# SOM_AB.net
KiCad netlist of a schematic drawn in Altium Designer
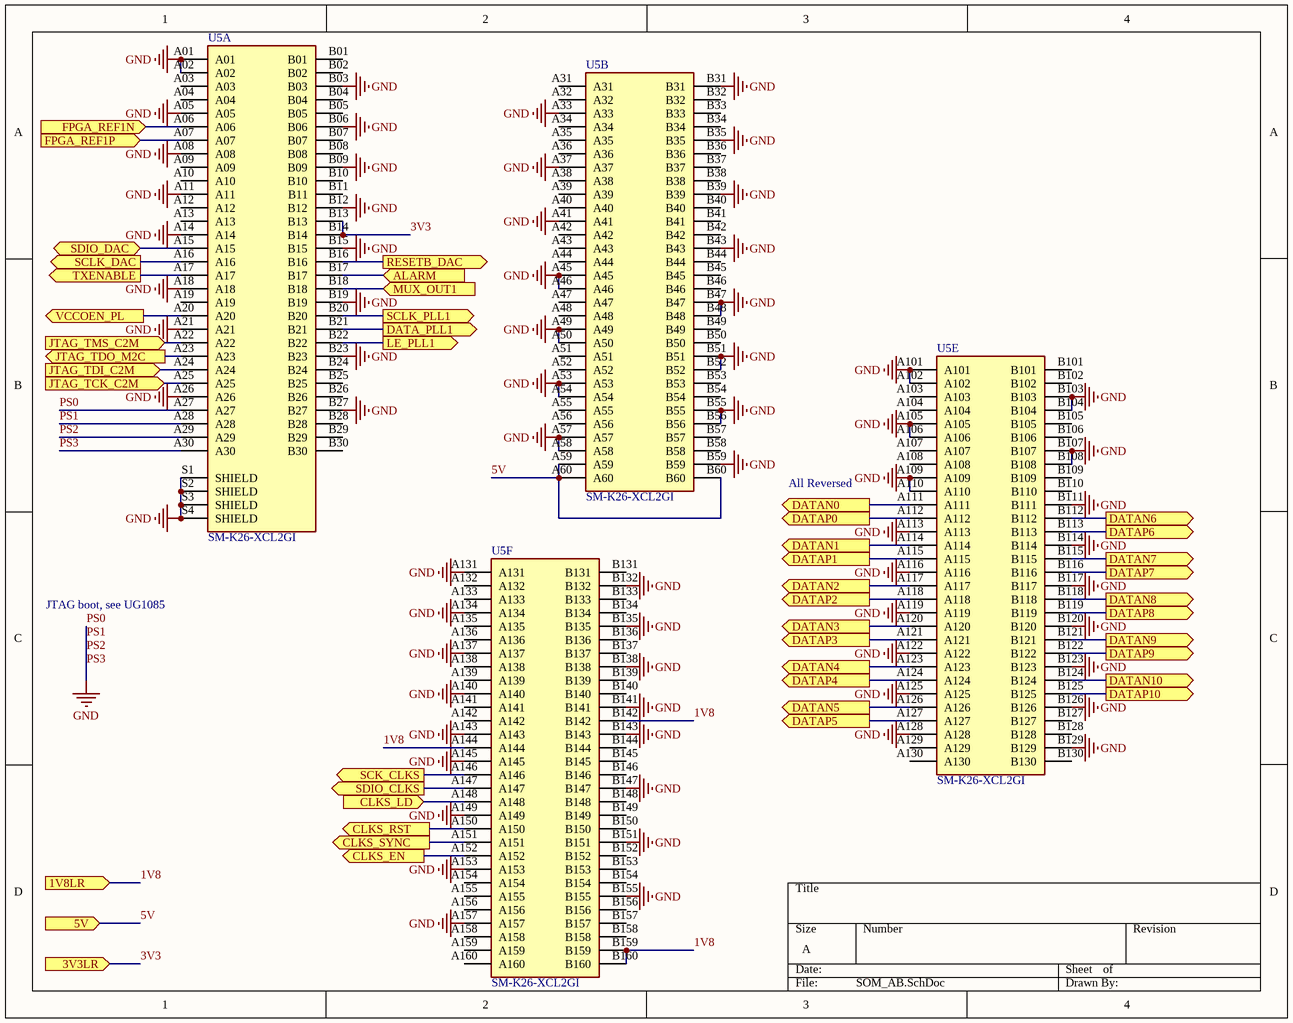
[diagram p0: SOM_AB.SchDoc]

(export (version "E")
  (design (tool "Eeschema 10.0.6"))
  (components
    (comp (ref "U5")
      (value "SM-K26-XCL2GI")
      (footprint "MODULE_SM-K26-XCL2GI")
      (fields (field (name "MF") "Xilinx Inc."))
      (libsource (lib "SM-K26-XCL2GI") (part "SM-K26-XCL2GI"))
    )
  )
  (nets
    (net (code "1") (name "/1V8") (class "Default")
      (node (ref "U5") (pin "A144") (pinfunction "A144_A144") (pintype "passive"))
      (node (ref "U5") (pin "B142") (pinfunction "B142_B142") (pintype "passive"))
      (node (ref "U5") (pin "B159") (pinfunction "B159_B159") (pintype "passive"))
      (node (ref "U5") (pin "B160") (pinfunction "B160_B160") (pintype "passive"))
    )
    (net (code "2") (name "/3V3") (class "Default")
      (node (ref "U5") (pin "B13") (pinfunction "B13_B13") (pintype "passive"))
      (node (ref "U5") (pin "B14") (pinfunction "B14_B14") (pintype "passive"))
    )
    (net (code "3") (name "/5V") (class "Default")
      (node (ref "U5") (pin "A59") (pinfunction "A59_A59") (pintype "passive"))
      (node (ref "U5") (pin "A60") (pinfunction "A60_A60") (pintype "passive"))
      (node (ref "U5") (pin "B60") (pinfunction "B60_B60") (pintype "passive"))
    )
    (net (code "4") (name "/ALARM") (class "Default")
      (node (ref "U5") (pin "B17") (pinfunction "B17_B17") (pintype "passive"))
    )
    (net (code "5") (name "/CLKS_EN") (class "Default")
      (node (ref "U5") (pin "A152") (pinfunction "A152_A152") (pintype "passive"))
    )
    (net (code "6") (name "/CLKS_LD") (class "Default")
      (node (ref "U5") (pin "A148") (pinfunction "A148_A148") (pintype "passive"))
    )
    (net (code "7") (name "/CLKS_RST") (class "Default")
      (node (ref "U5") (pin "A150") (pinfunction "A150_A150") (pintype "passive"))
    )
    (net (code "8") (name "/CLKS_SYNC") (class "Default")
      (node (ref "U5") (pin "A151") (pinfunction "A151_A151") (pintype "passive"))
    )
    (net (code "9") (name "/DATAN0") (class "Default")
      (node (ref "U5") (pin "A111") (pinfunction "A111_A111") (pintype "passive"))
    )
    (net (code "10") (name "/DATAN1") (class "Default")
      (node (ref "U5") (pin "A114") (pinfunction "A114_A114") (pintype "passive"))
    )
    (net (code "11") (name "/DATAN2") (class "Default")
      (node (ref "U5") (pin "A117") (pinfunction "A117_A117") (pintype "passive"))
    )
    (net (code "12") (name "/DATAN3") (class "Default")
      (node (ref "U5") (pin "A120") (pinfunction "A120_A120") (pintype "passive"))
    )
    (net (code "13") (name "/DATAN4") (class "Default")
      (node (ref "U5") (pin "A123") (pinfunction "A123_A123") (pintype "passive"))
    )
    (net (code "14") (name "/DATAN5") (class "Default")
      (node (ref "U5") (pin "A126") (pinfunction "A126_A126") (pintype "passive"))
    )
    (net (code "15") (name "/DATAN6") (class "Default")
      (node (ref "U5") (pin "B112") (pinfunction "B112_B112") (pintype "passive"))
    )
    (net (code "16") (name "/DATAN7") (class "Default")
      (node (ref "U5") (pin "B115") (pinfunction "B115_B115") (pintype "passive"))
    )
    (net (code "17") (name "/DATAN8") (class "Default")
      (node (ref "U5") (pin "B118") (pinfunction "B118_B118") (pintype "passive"))
    )
    (net (code "18") (name "/DATAN9") (class "Default")
      (node (ref "U5") (pin "B121") (pinfunction "B121_B121") (pintype "passive"))
    )
    (net (code "19") (name "/DATAN10") (class "Default")
      (node (ref "U5") (pin "B124") (pinfunction "B124_B124") (pintype "passive"))
    )
    (net (code "20") (name "/DATAP0") (class "Default")
      (node (ref "U5") (pin "A112") (pinfunction "A112_A112") (pintype "passive"))
    )
    (net (code "21") (name "/DATAP1") (class "Default")
      (node (ref "U5") (pin "A115") (pinfunction "A115_A115") (pintype "passive"))
    )
    (net (code "22") (name "/DATAP2") (class "Default")
      (node (ref "U5") (pin "A118") (pinfunction "A118_A118") (pintype "passive"))
    )
    (net (code "23") (name "/DATAP3") (class "Default")
      (node (ref "U5") (pin "A121") (pinfunction "A121_A121") (pintype "passive"))
    )
    (net (code "24") (name "/DATAP4") (class "Default")
      (node (ref "U5") (pin "A124") (pinfunction "A124_A124") (pintype "passive"))
    )
    (net (code "25") (name "/DATAP5") (class "Default")
      (node (ref "U5") (pin "A127") (pinfunction "A127_A127") (pintype "passive"))
    )
    (net (code "26") (name "/DATAP6") (class "Default")
      (node (ref "U5") (pin "B113") (pinfunction "B113_B113") (pintype "passive"))
    )
    (net (code "27") (name "/DATAP7") (class "Default")
      (node (ref "U5") (pin "B116") (pinfunction "B116_B116") (pintype "passive"))
    )
    (net (code "28") (name "/DATAP8") (class "Default")
      (node (ref "U5") (pin "B119") (pinfunction "B119_B119") (pintype "passive"))
    )
    (net (code "29") (name "/DATAP9") (class "Default")
      (node (ref "U5") (pin "B122") (pinfunction "B122_B122") (pintype "passive"))
    )
    (net (code "30") (name "/DATAP10") (class "Default")
      (node (ref "U5") (pin "B125") (pinfunction "B125_B125") (pintype "passive"))
    )
    (net (code "31") (name "/DATA_PLL1") (class "Default")
      (node (ref "U5") (pin "B21") (pinfunction "B21_B21") (pintype "passive"))
    )
    (net (code "32") (name "/FPGA_REF1N") (class "Default")
      (node (ref "U5") (pin "A06") (pinfunction "A06_A06") (pintype "passive"))
    )
    (net (code "33") (name "/FPGA_REF1P") (class "Default")
      (node (ref "U5") (pin "A07") (pinfunction "A07_A07") (pintype "passive"))
    )
    (net (code "34") (name "/JTAG_TCK_C2M") (class "Default")
      (node (ref "U5") (pin "A25") (pinfunction "A25_A25") (pintype "passive"))
    )
    (net (code "35") (name "/JTAG_TDI_C2M") (class "Default")
      (node (ref "U5") (pin "A24") (pinfunction "A24_A24") (pintype "passive"))
    )
    (net (code "36") (name "/JTAG_TDO_M2C") (class "Default")
      (node (ref "U5") (pin "A23") (pinfunction "A23_A23") (pintype "passive"))
    )
    (net (code "37") (name "/JTAG_TMS_C2M") (class "Default")
      (node (ref "U5") (pin "A22") (pinfunction "A22_A22") (pintype "passive"))
    )
    (net (code "38") (name "/LE_PLL1") (class "Default")
      (node (ref "U5") (pin "B22") (pinfunction "B22_B22") (pintype "passive"))
    )
    (net (code "39") (name "/MUX_OUT1") (class "Default")
      (node (ref "U5") (pin "B18") (pinfunction "B18_B18") (pintype "passive"))
    )
    (net (code "40") (name "/RESETB_DAC") (class "Default")
      (node (ref "U5") (pin "B16") (pinfunction "B16_B16") (pintype "passive"))
    )
    (net (code "41") (name "/SCK_CLKS") (class "Default")
      (node (ref "U5") (pin "A146") (pinfunction "A146_A146") (pintype "passive"))
    )
    (net (code "42") (name "/SCLK_DAC") (class "Default")
      (node (ref "U5") (pin "A16") (pinfunction "A16_A16") (pintype "passive"))
    )
    (net (code "43") (name "/SCLK_PLL1") (class "Default")
      (node (ref "U5") (pin "B20") (pinfunction "B20_B20") (pintype "passive"))
    )
    (net (code "44") (name "/SDIO_CLKS") (class "Default")
      (node (ref "U5") (pin "A147") (pinfunction "A147_A147") (pintype "passive"))
    )
    (net (code "45") (name "/SDIO_DAC") (class "Default")
      (node (ref "U5") (pin "A15") (pinfunction "A15_A15") (pintype "passive"))
    )
    (net (code "46") (name "/TXENABLE") (class "Default")
      (node (ref "U5") (pin "A17") (pinfunction "A17_A17") (pintype "passive"))
    )
    (net (code "47") (name "/VCCOEN_PL") (class "Default")
      (node (ref "U5") (pin "A20") (pinfunction "A20_A20") (pintype "passive"))
    )
    (net (code "48") (name "GND") (class "Default")
      (node (ref "U5") (pin "A01") (pinfunction "A01_A01") (pintype "passive"))
      (node (ref "U5") (pin "A02") (pinfunction "A02_A02") (pintype "passive"))
      (node (ref "U5") (pin "A05") (pinfunction "A05_A05") (pintype "passive"))
      (node (ref "U5") (pin "A08") (pinfunction "A08_A08") (pintype "passive"))
      (node (ref "U5") (pin "A101") (pinfunction "A101_A101") (pintype "passive"))
      (node (ref "U5") (pin "A102") (pinfunction "A102_A102") (pintype "passive"))
      (node (ref "U5") (pin "A105") (pinfunction "A105_A105") (pintype "passive"))
      (node (ref "U5") (pin "A106") (pinfunction "A106_A106") (pintype "passive"))
      (node (ref "U5") (pin "A109") (pinfunction "A109_A109") (pintype "passive"))
      (node (ref "U5") (pin "A11") (pinfunction "A11_A11") (pintype "passive"))
      (node (ref "U5") (pin "A110") (pinfunction "A110_A110") (pintype "passive"))
      (node (ref "U5") (pin "A113") (pinfunction "A113_A113") (pintype "passive"))
      (node (ref "U5") (pin "A116") (pinfunction "A116_A116") (pintype "passive"))
      (node (ref "U5") (pin "A119") (pinfunction "A119_A119") (pintype "passive"))
      (node (ref "U5") (pin "A122") (pinfunction "A122_A122") (pintype "passive"))
      (node (ref "U5") (pin "A125") (pinfunction "A125_A125") (pintype "passive"))
      (node (ref "U5") (pin "A128") (pinfunction "A128_A128") (pintype "passive"))
      (node (ref "U5") (pin "A131") (pinfunction "A131_A131") (pintype "passive"))
      (node (ref "U5") (pin "A134") (pinfunction "A134_A134") (pintype "passive"))
      (node (ref "U5") (pin "A137") (pinfunction "A137_A137") (pintype "passive"))
      (node (ref "U5") (pin "A14") (pinfunction "A14_A14") (pintype "passive"))
      (node (ref "U5") (pin "A140") (pinfunction "A140_A140") (pintype "passive"))
      (node (ref "U5") (pin "A143") (pinfunction "A143_A143") (pintype "passive"))
      (node (ref "U5") (pin "A145") (pinfunction "A145_A145") (pintype "passive"))
      (node (ref "U5") (pin "A149") (pinfunction "A149_A149") (pintype "passive"))
      (node (ref "U5") (pin "A153") (pinfunction "A153_A153") (pintype "passive"))
      (node (ref "U5") (pin "A157") (pinfunction "A157_A157") (pintype "passive"))
      (node (ref "U5") (pin "A18") (pinfunction "A18_A18") (pintype "passive"))
      (node (ref "U5") (pin "A21") (pinfunction "A21_A21") (pintype "passive"))
      (node (ref "U5") (pin "A26") (pinfunction "A26_A26") (pintype "passive"))
      (node (ref "U5") (pin "A27") (pinfunction "A27_A27") (pintype "passive"))
      (node (ref "U5") (pin "A28") (pinfunction "A28_A28") (pintype "passive"))
      (node (ref "U5") (pin "A29") (pinfunction "A29_A29") (pintype "passive"))
      (node (ref "U5") (pin "A30") (pinfunction "A30_A30") (pintype "passive"))
      (node (ref "U5") (pin "A33") (pinfunction "A33_A33") (pintype "passive"))
      (node (ref "U5") (pin "A37") (pinfunction "A37_A37") (pintype "passive"))
      (node (ref "U5") (pin "A41") (pinfunction "A41_A41") (pintype "passive"))
      (node (ref "U5") (pin "A45") (pinfunction "A45_A45") (pintype "passive"))
      (node (ref "U5") (pin "A46") (pinfunction "A46_A46") (pintype "passive"))
      (node (ref "U5") (pin "A49") (pinfunction "A49_A49") (pintype "passive"))
      (node (ref "U5") (pin "A50") (pinfunction "A50_A50") (pintype "passive"))
      (node (ref "U5") (pin "A53") (pinfunction "A53_A53") (pintype "passive"))
      (node (ref "U5") (pin "A54") (pinfunction "A54_A54") (pintype "passive"))
      (node (ref "U5") (pin "A57") (pinfunction "A57_A57") (pintype "passive"))
      (node (ref "U5") (pin "A58") (pinfunction "A58_A58") (pintype "passive"))
      (node (ref "U5") (pin "B03") (pinfunction "B03_B03") (pintype "passive"))
      (node (ref "U5") (pin "B06") (pinfunction "B06_B06") (pintype "passive"))
      (node (ref "U5") (pin "B09") (pinfunction "B09_B09") (pintype "passive"))
      (node (ref "U5") (pin "B103") (pinfunction "B103_B103") (pintype "passive"))
      (node (ref "U5") (pin "B104") (pinfunction "B104_B104") (pintype "passive"))
      (node (ref "U5") (pin "B107") (pinfunction "B107_B107") (pintype "passive"))
      (node (ref "U5") (pin "B108") (pinfunction "B108_B108") (pintype "passive"))
      (node (ref "U5") (pin "B111") (pinfunction "B111_B111") (pintype "passive"))
      (node (ref "U5") (pin "B114") (pinfunction "B114_B114") (pintype "passive"))
      (node (ref "U5") (pin "B117") (pinfunction "B117_B117") (pintype "passive"))
      (node (ref "U5") (pin "B12") (pinfunction "B12_B12") (pintype "passive"))
      (node (ref "U5") (pin "B120") (pinfunction "B120_B120") (pintype "passive"))
      (node (ref "U5") (pin "B123") (pinfunction "B123_B123") (pintype "passive"))
      (node (ref "U5") (pin "B126") (pinfunction "B126_B126") (pintype "passive"))
      (node (ref "U5") (pin "B129") (pinfunction "B129_B129") (pintype "passive"))
      (node (ref "U5") (pin "B132") (pinfunction "B132_B132") (pintype "passive"))
      (node (ref "U5") (pin "B135") (pinfunction "B135_B135") (pintype "passive"))
      (node (ref "U5") (pin "B138") (pinfunction "B138_B138") (pintype "passive"))
      (node (ref "U5") (pin "B141") (pinfunction "B141_B141") (pintype "passive"))
      (node (ref "U5") (pin "B143") (pinfunction "B143_B143") (pintype "passive"))
      (node (ref "U5") (pin "B147") (pinfunction "B147_B147") (pintype "passive"))
      (node (ref "U5") (pin "B15") (pinfunction "B15_B15") (pintype "passive"))
      (node (ref "U5") (pin "B151") (pinfunction "B151_B151") (pintype "passive"))
      (node (ref "U5") (pin "B155") (pinfunction "B155_B155") (pintype "passive"))
      (node (ref "U5") (pin "B19") (pinfunction "B19_B19") (pintype "passive"))
      (node (ref "U5") (pin "B23") (pinfunction "B23_B23") (pintype "passive"))
      (node (ref "U5") (pin "B27") (pinfunction "B27_B27") (pintype "passive"))
      (node (ref "U5") (pin "B31") (pinfunction "B31_B31") (pintype "passive"))
      (node (ref "U5") (pin "B35") (pinfunction "B35_B35") (pintype "passive"))
      (node (ref "U5") (pin "B39") (pinfunction "B39_B39") (pintype "passive"))
      (node (ref "U5") (pin "B43") (pinfunction "B43_B43") (pintype "passive"))
      (node (ref "U5") (pin "B47") (pinfunction "B47_B47") (pintype "passive"))
      (node (ref "U5") (pin "B48") (pinfunction "B48_B48") (pintype "passive"))
      (node (ref "U5") (pin "B51") (pinfunction "B51_B51") (pintype "passive"))
      (node (ref "U5") (pin "B52") (pinfunction "B52_B52") (pintype "passive"))
      (node (ref "U5") (pin "B55") (pinfunction "B55_B55") (pintype "passive"))
      (node (ref "U5") (pin "B56") (pinfunction "B56_B56") (pintype "passive"))
      (node (ref "U5") (pin "B59") (pinfunction "B59_B59") (pintype "passive"))
      (node (ref "U5") (pin "S1") (pinfunction "SHIELD_S1") (pintype "passive"))
      (node (ref "U5") (pin "S2") (pinfunction "SHIELD_S2") (pintype "passive"))
      (node (ref "U5") (pin "S3") (pinfunction "SHIELD_S3") (pintype "passive"))
      (node (ref "U5") (pin "S4") (pinfunction "SHIELD_S4") (pintype "passive"))
    )
    (net (code "49") (name "unconnected-(U5-PadA03)") (class "Default")
      (node (ref "U5") (pin "A03") (pinfunction "A03_A03") (pintype "passive"))
    )
    (net (code "50") (name "unconnected-(U5-PadA04)") (class "Default")
      (node (ref "U5") (pin "A04") (pinfunction "A04_A04") (pintype "passive"))
    )
    (net (code "51") (name "unconnected-(U5-PadA09)") (class "Default")
      (node (ref "U5") (pin "A09") (pinfunction "A09_A09") (pintype "passive"))
    )
    (net (code "52") (name "unconnected-(U5-PadA10)") (class "Default")
      (node (ref "U5") (pin "A10") (pinfunction "A10_A10") (pintype "passive"))
    )
    (net (code "53") (name "unconnected-(U5-PadA12)") (class "Default")
      (node (ref "U5") (pin "A12") (pinfunction "A12_A12") (pintype "passive"))
    )
    (net (code "54") (name "unconnected-(U5-PadA13)") (class "Default")
      (node (ref "U5") (pin "A13") (pinfunction "A13_A13") (pintype "passive"))
    )
    (net (code "55") (name "unconnected-(U5-PadA19)") (class "Default")
      (node (ref "U5") (pin "A19") (pinfunction "A19_A19") (pintype "passive"))
    )
    (net (code "56") (name "unconnected-(U5-PadA31)") (class "Default")
      (node (ref "U5") (pin "A31") (pinfunction "A31_A31") (pintype "passive"))
    )
    (net (code "57") (name "unconnected-(U5-PadA32)") (class "Default")
      (node (ref "U5") (pin "A32") (pinfunction "A32_A32") (pintype "passive"))
    )
    (net (code "58") (name "unconnected-(U5-PadA34)") (class "Default")
      (node (ref "U5") (pin "A34") (pinfunction "A34_A34") (pintype "passive"))
    )
    (net (code "59") (name "unconnected-(U5-PadA35)") (class "Default")
      (node (ref "U5") (pin "A35") (pinfunction "A35_A35") (pintype "passive"))
    )
    (net (code "60") (name "unconnected-(U5-PadA36)") (class "Default")
      (node (ref "U5") (pin "A36") (pinfunction "A36_A36") (pintype "passive"))
    )
    (net (code "61") (name "unconnected-(U5-PadA38)") (class "Default")
      (node (ref "U5") (pin "A38") (pinfunction "A38_A38") (pintype "passive"))
    )
    (net (code "62") (name "unconnected-(U5-PadA39)") (class "Default")
      (node (ref "U5") (pin "A39") (pinfunction "A39_A39") (pintype "passive"))
    )
    (net (code "63") (name "unconnected-(U5-PadA40)") (class "Default")
      (node (ref "U5") (pin "A40") (pinfunction "A40_A40") (pintype "passive"))
    )
    (net (code "64") (name "unconnected-(U5-PadA42)") (class "Default")
      (node (ref "U5") (pin "A42") (pinfunction "A42_A42") (pintype "passive"))
    )
    (net (code "65") (name "unconnected-(U5-PadA43)") (class "Default")
      (node (ref "U5") (pin "A43") (pinfunction "A43_A43") (pintype "passive"))
    )
    (net (code "66") (name "unconnected-(U5-PadA44)") (class "Default")
      (node (ref "U5") (pin "A44") (pinfunction "A44_A44") (pintype "passive"))
    )
    (net (code "67") (name "unconnected-(U5-PadA47)") (class "Default")
      (node (ref "U5") (pin "A47") (pinfunction "A47_A47") (pintype "passive"))
    )
    (net (code "68") (name "unconnected-(U5-PadA48)") (class "Default")
      (node (ref "U5") (pin "A48") (pinfunction "A48_A48") (pintype "passive"))
    )
    (net (code "69") (name "unconnected-(U5-PadA51)") (class "Default")
      (node (ref "U5") (pin "A51") (pinfunction "A51_A51") (pintype "passive"))
    )
    (net (code "70") (name "unconnected-(U5-PadA52)") (class "Default")
      (node (ref "U5") (pin "A52") (pinfunction "A52_A52") (pintype "passive"))
    )
    (net (code "71") (name "unconnected-(U5-PadA55)") (class "Default")
      (node (ref "U5") (pin "A55") (pinfunction "A55_A55") (pintype "passive"))
    )
    (net (code "72") (name "unconnected-(U5-PadA56)") (class "Default")
      (node (ref "U5") (pin "A56") (pinfunction "A56_A56") (pintype "passive"))
    )
    (net (code "73") (name "unconnected-(U5-PadA103)") (class "Default")
      (node (ref "U5") (pin "A103") (pinfunction "A103_A103") (pintype "passive"))
    )
    (net (code "74") (name "unconnected-(U5-PadA104)") (class "Default")
      (node (ref "U5") (pin "A104") (pinfunction "A104_A104") (pintype "passive"))
    )
    (net (code "75") (name "unconnected-(U5-PadA107)") (class "Default")
      (node (ref "U5") (pin "A107") (pinfunction "A107_A107") (pintype "passive"))
    )
    (net (code "76") (name "unconnected-(U5-PadA108)") (class "Default")
      (node (ref "U5") (pin "A108") (pinfunction "A108_A108") (pintype "passive"))
    )
    (net (code "77") (name "unconnected-(U5-PadA129)") (class "Default")
      (node (ref "U5") (pin "A129") (pinfunction "A129_A129") (pintype "passive"))
    )
    (net (code "78") (name "unconnected-(U5-PadA130)") (class "Default")
      (node (ref "U5") (pin "A130") (pinfunction "A130_A130") (pintype "passive"))
    )
    (net (code "79") (name "unconnected-(U5-PadA132)") (class "Default")
      (node (ref "U5") (pin "A132") (pinfunction "A132_A132") (pintype "passive"))
    )
    (net (code "80") (name "unconnected-(U5-PadA133)") (class "Default")
      (node (ref "U5") (pin "A133") (pinfunction "A133_A133") (pintype "passive"))
    )
    (net (code "81") (name "unconnected-(U5-PadA135)") (class "Default")
      (node (ref "U5") (pin "A135") (pinfunction "A135_A135") (pintype "passive"))
    )
    (net (code "82") (name "unconnected-(U5-PadA136)") (class "Default")
      (node (ref "U5") (pin "A136") (pinfunction "A136_A136") (pintype "passive"))
    )
    (net (code "83") (name "unconnected-(U5-PadA138)") (class "Default")
      (node (ref "U5") (pin "A138") (pinfunction "A138_A138") (pintype "passive"))
    )
    (net (code "84") (name "unconnected-(U5-PadA139)") (class "Default")
      (node (ref "U5") (pin "A139") (pinfunction "A139_A139") (pintype "passive"))
    )
    (net (code "85") (name "unconnected-(U5-PadA141)") (class "Default")
      (node (ref "U5") (pin "A141") (pinfunction "A141_A141") (pintype "passive"))
    )
    (net (code "86") (name "unconnected-(U5-PadA142)") (class "Default")
      (node (ref "U5") (pin "A142") (pinfunction "A142_A142") (pintype "passive"))
    )
    (net (code "87") (name "unconnected-(U5-PadA154)") (class "Default")
      (node (ref "U5") (pin "A154") (pinfunction "A154_A154") (pintype "passive"))
    )
    (net (code "88") (name "unconnected-(U5-PadA155)") (class "Default")
      (node (ref "U5") (pin "A155") (pinfunction "A155_A155") (pintype "passive"))
    )
    (net (code "89") (name "unconnected-(U5-PadA156)") (class "Default")
      (node (ref "U5") (pin "A156") (pinfunction "A156_A156") (pintype "passive"))
    )
    (net (code "90") (name "unconnected-(U5-PadA158)") (class "Default")
      (node (ref "U5") (pin "A158") (pinfunction "A158_A158") (pintype "passive"))
    )
    (net (code "91") (name "unconnected-(U5-PadA159)") (class "Default")
      (node (ref "U5") (pin "A159") (pinfunction "A159_A159") (pintype "passive"))
    )
    (net (code "92") (name "unconnected-(U5-PadA160)") (class "Default")
      (node (ref "U5") (pin "A160") (pinfunction "A160_A160") (pintype "passive"))
    )
    (net (code "93") (name "unconnected-(U5-PadB01)") (class "Default")
      (node (ref "U5") (pin "B01") (pinfunction "B01_B01") (pintype "passive"))
    )
    (net (code "94") (name "unconnected-(U5-PadB02)") (class "Default")
      (node (ref "U5") (pin "B02") (pinfunction "B02_B02") (pintype "passive"))
    )
    (net (code "95") (name "unconnected-(U5-PadB04)") (class "Default")
      (node (ref "U5") (pin "B04") (pinfunction "B04_B04") (pintype "passive"))
    )
    (net (code "96") (name "unconnected-(U5-PadB05)") (class "Default")
      (node (ref "U5") (pin "B05") (pinfunction "B05_B05") (pintype "passive"))
    )
    (net (code "97") (name "unconnected-(U5-PadB07)") (class "Default")
      (node (ref "U5") (pin "B07") (pinfunction "B07_B07") (pintype "passive"))
    )
    (net (code "98") (name "unconnected-(U5-PadB08)") (class "Default")
      (node (ref "U5") (pin "B08") (pinfunction "B08_B08") (pintype "passive"))
    )
    (net (code "99") (name "unconnected-(U5-PadB10)") (class "Default")
      (node (ref "U5") (pin "B10") (pinfunction "B10_B10") (pintype "passive"))
    )
    (net (code "100") (name "unconnected-(U5-PadB11)") (class "Default")
      (node (ref "U5") (pin "B11") (pinfunction "B11_B11") (pintype "passive"))
    )
    (net (code "101") (name "unconnected-(U5-PadB24)") (class "Default")
      (node (ref "U5") (pin "B24") (pinfunction "B24_B24") (pintype "passive"))
    )
    (net (code "102") (name "unconnected-(U5-PadB25)") (class "Default")
      (node (ref "U5") (pin "B25") (pinfunction "B25_B25") (pintype "passive"))
    )
    (net (code "103") (name "unconnected-(U5-PadB26)") (class "Default")
      (node (ref "U5") (pin "B26") (pinfunction "B26_B26") (pintype "passive"))
    )
    (net (code "104") (name "unconnected-(U5-PadB28)") (class "Default")
      (node (ref "U5") (pin "B28") (pinfunction "B28_B28") (pintype "passive"))
    )
    (net (code "105") (name "unconnected-(U5-PadB29)") (class "Default")
      (node (ref "U5") (pin "B29") (pinfunction "B29_B29") (pintype "passive"))
    )
    (net (code "106") (name "unconnected-(U5-PadB30)") (class "Default")
      (node (ref "U5") (pin "B30") (pinfunction "B30_B30") (pintype "passive"))
    )
    (net (code "107") (name "unconnected-(U5-PadB32)") (class "Default")
      (node (ref "U5") (pin "B32") (pinfunction "B32_B32") (pintype "passive"))
    )
    (net (code "108") (name "unconnected-(U5-PadB33)") (class "Default")
      (node (ref "U5") (pin "B33") (pinfunction "B33_B33") (pintype "passive"))
    )
    (net (code "109") (name "unconnected-(U5-PadB34)") (class "Default")
      (node (ref "U5") (pin "B34") (pinfunction "B34_B34") (pintype "passive"))
    )
    (net (code "110") (name "unconnected-(U5-PadB36)") (class "Default")
      (node (ref "U5") (pin "B36") (pinfunction "B36_B36") (pintype "passive"))
    )
    (net (code "111") (name "unconnected-(U5-PadB37)") (class "Default")
      (node (ref "U5") (pin "B37") (pinfunction "B37_B37") (pintype "passive"))
    )
    (net (code "112") (name "unconnected-(U5-PadB38)") (class "Default")
      (node (ref "U5") (pin "B38") (pinfunction "B38_B38") (pintype "passive"))
    )
    (net (code "113") (name "unconnected-(U5-PadB40)") (class "Default")
      (node (ref "U5") (pin "B40") (pinfunction "B40_B40") (pintype "passive"))
    )
    (net (code "114") (name "unconnected-(U5-PadB41)") (class "Default")
      (node (ref "U5") (pin "B41") (pinfunction "B41_B41") (pintype "passive"))
    )
    (net (code "115") (name "unconnected-(U5-PadB42)") (class "Default")
      (node (ref "U5") (pin "B42") (pinfunction "B42_B42") (pintype "passive"))
    )
    (net (code "116") (name "unconnected-(U5-PadB44)") (class "Default")
      (node (ref "U5") (pin "B44") (pinfunction "B44_B44") (pintype "passive"))
    )
    (net (code "117") (name "unconnected-(U5-PadB45)") (class "Default")
      (node (ref "U5") (pin "B45") (pinfunction "B45_B45") (pintype "passive"))
    )
    (net (code "118") (name "unconnected-(U5-PadB46)") (class "Default")
      (node (ref "U5") (pin "B46") (pinfunction "B46_B46") (pintype "passive"))
    )
    (net (code "119") (name "unconnected-(U5-PadB49)") (class "Default")
      (node (ref "U5") (pin "B49") (pinfunction "B49_B49") (pintype "passive"))
    )
    (net (code "120") (name "unconnected-(U5-PadB50)") (class "Default")
      (node (ref "U5") (pin "B50") (pinfunction "B50_B50") (pintype "passive"))
    )
    (net (code "121") (name "unconnected-(U5-PadB53)") (class "Default")
      (node (ref "U5") (pin "B53") (pinfunction "B53_B53") (pintype "passive"))
    )
    (net (code "122") (name "unconnected-(U5-PadB54)") (class "Default")
      (node (ref "U5") (pin "B54") (pinfunction "B54_B54") (pintype "passive"))
    )
    (net (code "123") (name "unconnected-(U5-PadB57)") (class "Default")
      (node (ref "U5") (pin "B57") (pinfunction "B57_B57") (pintype "passive"))
    )
    (net (code "124") (name "unconnected-(U5-PadB58)") (class "Default")
      (node (ref "U5") (pin "B58") (pinfunction "B58_B58") (pintype "passive"))
    )
    (net (code "125") (name "unconnected-(U5-PadB101)") (class "Default")
      (node (ref "U5") (pin "B101") (pinfunction "B101_B101") (pintype "passive"))
    )
    (net (code "126") (name "unconnected-(U5-PadB102)") (class "Default")
      (node (ref "U5") (pin "B102") (pinfunction "B102_B102") (pintype "passive"))
    )
    (net (code "127") (name "unconnected-(U5-PadB105)") (class "Default")
      (node (ref "U5") (pin "B105") (pinfunction "B105_B105") (pintype "passive"))
    )
    (net (code "128") (name "unconnected-(U5-PadB106)") (class "Default")
      (node (ref "U5") (pin "B106") (pinfunction "B106_B106") (pintype "passive"))
    )
    (net (code "129") (name "unconnected-(U5-PadB109)") (class "Default")
      (node (ref "U5") (pin "B109") (pinfunction "B109_B109") (pintype "passive"))
    )
    (net (code "130") (name "unconnected-(U5-PadB110)") (class "Default")
      (node (ref "U5") (pin "B110") (pinfunction "B110_B110") (pintype "passive"))
    )
    (net (code "131") (name "unconnected-(U5-PadB127)") (class "Default")
      (node (ref "U5") (pin "B127") (pinfunction "B127_B127") (pintype "passive"))
    )
    (net (code "132") (name "unconnected-(U5-PadB128)") (class "Default")
      (node (ref "U5") (pin "B128") (pinfunction "B128_B128") (pintype "passive"))
    )
    (net (code "133") (name "unconnected-(U5-PadB130)") (class "Default")
      (node (ref "U5") (pin "B130") (pinfunction "B130_B130") (pintype "passive"))
    )
    (net (code "134") (name "unconnected-(U5-PadB131)") (class "Default")
      (node (ref "U5") (pin "B131") (pinfunction "B131_B131") (pintype "passive"))
    )
    (net (code "135") (name "unconnected-(U5-PadB133)") (class "Default")
      (node (ref "U5") (pin "B133") (pinfunction "B133_B133") (pintype "passive"))
    )
    (net (code "136") (name "unconnected-(U5-PadB134)") (class "Default")
      (node (ref "U5") (pin "B134") (pinfunction "B134_B134") (pintype "passive"))
    )
    (net (code "137") (name "unconnected-(U5-PadB136)") (class "Default")
      (node (ref "U5") (pin "B136") (pinfunction "B136_B136") (pintype "passive"))
    )
    (net (code "138") (name "unconnected-(U5-PadB137)") (class "Default")
      (node (ref "U5") (pin "B137") (pinfunction "B137_B137") (pintype "passive"))
    )
    (net (code "139") (name "unconnected-(U5-PadB139)") (class "Default")
      (node (ref "U5") (pin "B139") (pinfunction "B139_B139") (pintype "passive"))
    )
    (net (code "140") (name "unconnected-(U5-PadB140)") (class "Default")
      (node (ref "U5") (pin "B140") (pinfunction "B140_B140") (pintype "passive"))
    )
    (net (code "141") (name "unconnected-(U5-PadB144)") (class "Default")
      (node (ref "U5") (pin "B144") (pinfunction "B144_B144") (pintype "passive"))
    )
    (net (code "142") (name "unconnected-(U5-PadB145)") (class "Default")
      (node (ref "U5") (pin "B145") (pinfunction "B145_B145") (pintype "passive"))
    )
    (net (code "143") (name "unconnected-(U5-PadB146)") (class "Default")
      (node (ref "U5") (pin "B146") (pinfunction "B146_B146") (pintype "passive"))
    )
    (net (code "144") (name "unconnected-(U5-PadB148)") (class "Default")
      (node (ref "U5") (pin "B148") (pinfunction "B148_B148") (pintype "passive"))
    )
    (net (code "145") (name "unconnected-(U5-PadB149)") (class "Default")
      (node (ref "U5") (pin "B149") (pinfunction "B149_B149") (pintype "passive"))
    )
    (net (code "146") (name "unconnected-(U5-PadB150)") (class "Default")
      (node (ref "U5") (pin "B150") (pinfunction "B150_B150") (pintype "passive"))
    )
    (net (code "147") (name "unconnected-(U5-PadB152)") (class "Default")
      (node (ref "U5") (pin "B152") (pinfunction "B152_B152") (pintype "passive"))
    )
    (net (code "148") (name "unconnected-(U5-PadB153)") (class "Default")
      (node (ref "U5") (pin "B153") (pinfunction "B153_B153") (pintype "passive"))
    )
    (net (code "149") (name "unconnected-(U5-PadB154)") (class "Default")
      (node (ref "U5") (pin "B154") (pinfunction "B154_B154") (pintype "passive"))
    )
    (net (code "150") (name "unconnected-(U5-PadB156)") (class "Default")
      (node (ref "U5") (pin "B156") (pinfunction "B156_B156") (pintype "passive"))
    )
    (net (code "151") (name "unconnected-(U5-PadB157)") (class "Default")
      (node (ref "U5") (pin "B157") (pinfunction "B157_B157") (pintype "passive"))
    )
    (net (code "152") (name "unconnected-(U5-PadB158)") (class "Default")
      (node (ref "U5") (pin "B158") (pinfunction "B158_B158") (pintype "passive"))
    )
  )
)
